# hx711-RJ12-board.net
KiCad netlist of a schematic drawn in EAGLE
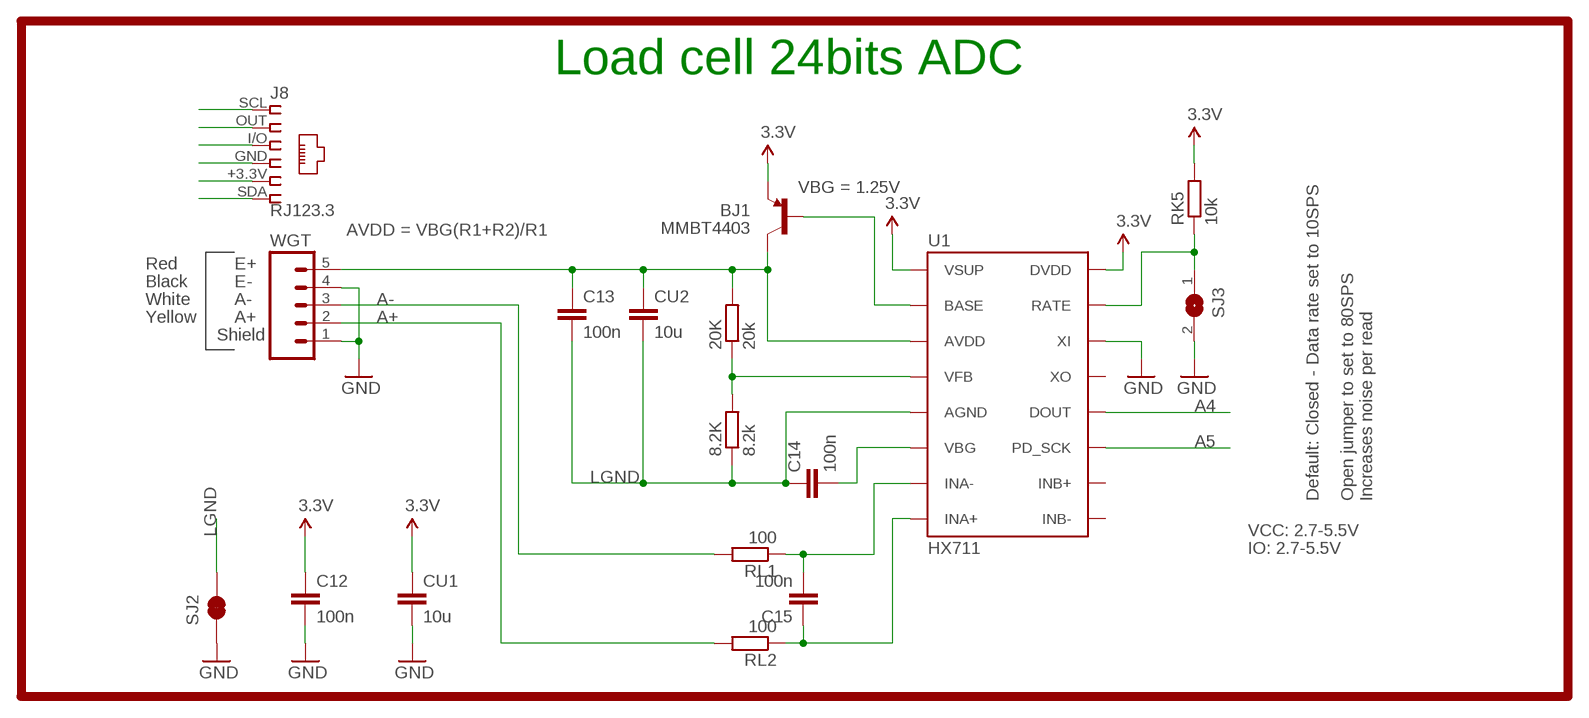
[diagram p0: schematic, sheet 1]

(export (version "E")
  (design (tool "Eeschema 10.0.6"))
  (components
    (comp (ref "8.2K")
      (value "8.2k")
      (footprint "eagle-import:M0805")
      (libsource (lib "eagle-import") (part "R-EU_M0805"))
    )
    (comp (ref "20K")
      (value "20k")
      (footprint "eagle-import:M0805")
      (libsource (lib "eagle-import") (part "R-EU_M0805"))
    )
    (comp (ref "BJ1")
      (value "MMBT4403")
      (footprint "eagle-import:SOT23-3")
      (libsource (lib "eagle-import") (part "TRANSISTOR_PNPMMBT4403"))
    )
    (comp (ref "C12")
      (value "100n")
      (footprint "eagle-import:C0805")
      (libsource (lib "eagle-import") (part "C-EUC0805"))
    )
    (comp (ref "C13")
      (value "100n")
      (footprint "eagle-import:C0805")
      (libsource (lib "eagle-import") (part "C-EUC0805"))
    )
    (comp (ref "C14")
      (value "100n")
      (footprint "eagle-import:C0805")
      (libsource (lib "eagle-import") (part "C-EUC0805"))
    )
    (comp (ref "C15")
      (value "100n")
      (footprint "eagle-import:C0805")
      (libsource (lib "eagle-import") (part "C-EUC0805"))
    )
    (comp (ref "CU1")
      (value "10u")
      (footprint "eagle-import:C0805")
      (libsource (lib "eagle-import") (part "C-EUC0805"))
    )
    (comp (ref "CU2")
      (value "10u")
      (footprint "eagle-import:C0805")
      (libsource (lib "eagle-import") (part "C-EUC0805"))
    )
    (comp (ref "J8")
      (value "RJ123.3")
      (footprint "eagle-import:RJ12-STRAIGHT-3.3")
      (libsource (lib "eagle-import") (part "RJ123.3"))
    )
    (comp (ref "RK5")
      (value "10k")
      (footprint "eagle-import:M0805")
      (libsource (lib "eagle-import") (part "R-EU_M0805"))
    )
    (comp (ref "RL1")
      (value "100")
      (footprint "eagle-import:M0805")
      (libsource (lib "eagle-import") (part "R-EU_M0805"))
    )
    (comp (ref "RL2")
      (value "100")
      (footprint "eagle-import:M0805")
      (libsource (lib "eagle-import") (part "R-EU_M0805"))
    )
    (comp (ref "SJ2")
      (value "JUMPER-PAD-2-NC_BY_TRACE")
      (footprint "eagle-import:PAD-JUMPER-2-NC_BY_TRACE_YES_SILK")
      (libsource (lib "eagle-import") (part "JUMPER-PAD-2-NC_BY_TRACE"))
    )
    (comp (ref "SJ3") (value "SJ") (footprint "eagle-import:SJ") (libsource (lib "eagle-import") (part "SJ")))
    (comp (ref "U1")
      (value "HX711")
      (footprint "eagle-import:SO16")
      (libsource (lib "eagle-import") (part "HX711HX711"))
    )
    (comp (ref "WGT")
      (value "M05PTH")
      (footprint "eagle-import:1X05")
      (libsource (lib "eagle-import") (part "M05PTH"))
    )
  )
  (nets
    (net (code "1") (name "/A+") (class "Default")
      (node (ref "RL2") (pin "2") (pinfunction "2_2") (pintype "passive"))
      (node (ref "WGT") (pin "2") (pinfunction "2_2") (pintype "passive"))
    )
    (net (code "2") (name "/A-") (class "Default")
      (node (ref "RL1") (pin "2") (pinfunction "2_2") (pintype "passive"))
      (node (ref "WGT") (pin "3") (pinfunction "3_3") (pintype "passive"))
    )
    (net (code "3") (name "/A4") (class "Default")
      (node (ref "U1") (pin "12") (pinfunction "DOUT_12") (pintype "bidirectional"))
    )
    (net (code "4") (name "/A5") (class "Default")
      (node (ref "U1") (pin "11") (pinfunction "PD_SCK_11") (pintype "bidirectional"))
    )
    (net (code "5") (name "/LGND") (class "Default")
      (node (ref "8.2K") (pin "1") (pinfunction "1_1") (pintype "passive"))
      (node (ref "C13") (pin "2") (pinfunction "2_2") (pintype "passive"))
      (node (ref "C14") (pin "1") (pinfunction "1_1") (pintype "passive"))
      (node (ref "CU2") (pin "2") (pinfunction "2_2") (pintype "passive"))
      (node (ref "SJ2") (pin "2") (pinfunction "2_2") (pintype "passive"))
      (node (ref "U1") (pin "5") (pinfunction "AGND_5") (pintype "bidirectional"))
    )
    (net (code "6") (name "3.3V") (class "Default")
      (node (ref "BJ1") (pin "2") (pinfunction "E_2") (pintype "passive"))
      (node (ref "C12") (pin "1") (pinfunction "1_1") (pintype "passive"))
      (node (ref "CU1") (pin "1") (pinfunction "1_1") (pintype "passive"))
      (node (ref "RK5") (pin "2") (pinfunction "2_2") (pintype "passive"))
      (node (ref "U1") (pin "1") (pinfunction "VSUP_1") (pintype "bidirectional"))
      (node (ref "U1") (pin "16") (pinfunction "DVDD_16") (pintype "bidirectional"))
    )
    (net (code "7") (name "GND") (class "Default")
      (node (ref "C12") (pin "2") (pinfunction "2_2") (pintype "passive"))
      (node (ref "CU1") (pin "2") (pinfunction "2_2") (pintype "passive"))
      (node (ref "SJ2") (pin "1") (pinfunction "1_1") (pintype "passive"))
      (node (ref "SJ3") (pin "2") (pinfunction "2_2") (pintype "passive"))
      (node (ref "U1") (pin "14") (pinfunction "XI_14") (pintype "bidirectional"))
      (node (ref "WGT") (pin "1") (pinfunction "1_1") (pintype "passive"))
      (node (ref "WGT") (pin "4") (pinfunction "4_4") (pintype "passive"))
    )
    (net (code "8") (name "Net-(BJ1-B)") (class "Default")
      (node (ref "BJ1") (pin "1") (pinfunction "B_1") (pintype "passive"))
      (node (ref "U1") (pin "2") (pinfunction "BASE_2") (pintype "bidirectional"))
    )
    (net (code "9") (name "Net-(BJ1-C)") (class "Default")
      (node (ref "20K") (pin "2") (pinfunction "2_2") (pintype "passive"))
      (node (ref "BJ1") (pin "3") (pinfunction "C_3") (pintype "passive"))
      (node (ref "C13") (pin "1") (pinfunction "1_1") (pintype "passive"))
      (node (ref "CU2") (pin "1") (pinfunction "1_1") (pintype "passive"))
      (node (ref "U1") (pin "3") (pinfunction "AVDD_3") (pintype "bidirectional"))
      (node (ref "WGT") (pin "5") (pinfunction "5_5") (pintype "passive"))
    )
    (net (code "10") (name "Net-(U1-INA+)") (class "Default")
      (node (ref "C15") (pin "1") (pinfunction "1_1") (pintype "passive"))
      (node (ref "RL2") (pin "1") (pinfunction "1_1") (pintype "passive"))
      (node (ref "U1") (pin "8") (pinfunction "INA+_8") (pintype "bidirectional"))
    )
    (net (code "11") (name "Net-(U1-INA-)") (class "Default")
      (node (ref "C15") (pin "2") (pinfunction "2_2") (pintype "passive"))
      (node (ref "RL1") (pin "1") (pinfunction "1_1") (pintype "passive"))
      (node (ref "U1") (pin "7") (pinfunction "INA-_7") (pintype "bidirectional"))
    )
    (net (code "12") (name "Net-(U1-RATE)") (class "Default")
      (node (ref "RK5") (pin "1") (pinfunction "1_1") (pintype "passive"))
      (node (ref "SJ3") (pin "1") (pinfunction "1_1") (pintype "passive"))
      (node (ref "U1") (pin "15") (pinfunction "RATE_15") (pintype "bidirectional"))
    )
    (net (code "13") (name "Net-(U1-VBG)") (class "Default")
      (node (ref "C14") (pin "2") (pinfunction "2_2") (pintype "passive"))
      (node (ref "U1") (pin "6") (pinfunction "VBG_6") (pintype "bidirectional"))
    )
    (net (code "14") (name "Net-(U1-VFB)") (class "Default")
      (node (ref "20K") (pin "1") (pinfunction "1_1") (pintype "passive"))
      (node (ref "8.2K") (pin "2") (pinfunction "2_2") (pintype "passive"))
      (node (ref "U1") (pin "4") (pinfunction "VFB_4") (pintype "bidirectional"))
    )
    (net (code "15") (name "unconnected-(J8-1-PadSCL)") (class "Default")
      (node (ref "J8") (pin "SCL") (pinfunction "1_SCL") (pintype "bidirectional"))
    )
    (net (code "16") (name "unconnected-(J8-2-PadOUT)") (class "Default")
      (node (ref "J8") (pin "OUT") (pinfunction "2_OUT") (pintype "bidirectional"))
    )
    (net (code "17") (name "unconnected-(J8-3-PadI{slash}O)") (class "Default")
      (node (ref "J8") (pin "I/O") (pinfunction "3_I/O") (pintype "bidirectional"))
    )
    (net (code "18") (name "unconnected-(J8-4-PadGND)") (class "Default")
      (node (ref "J8") (pin "GND") (pinfunction "4_GND") (pintype "bidirectional"))
    )
    (net (code "19") (name "unconnected-(J8-5-Pad+3.3V)") (class "Default")
      (node (ref "J8") (pin "+3.3V") (pinfunction "5_+3.3V") (pintype "bidirectional"))
    )
    (net (code "20") (name "unconnected-(J8-6-PadSDA)") (class "Default")
      (node (ref "J8") (pin "SDA") (pinfunction "6_SDA") (pintype "bidirectional"))
    )
    (net (code "21") (name "unconnected-(U1-INB+-Pad10)") (class "Default")
      (node (ref "U1") (pin "10") (pinfunction "INB+_10") (pintype "bidirectional"))
    )
    (net (code "22") (name "unconnected-(U1-INB--Pad9)") (class "Default")
      (node (ref "U1") (pin "9") (pinfunction "INB-_9") (pintype "bidirectional"))
    )
    (net (code "23") (name "unconnected-(U1-XO-Pad13)") (class "Default")
      (node (ref "U1") (pin "13") (pinfunction "XO_13") (pintype "bidirectional"))
    )
  )
)
